# Battery_Management_System.net
KiCad netlist of a schematic drawn in Altium Designer
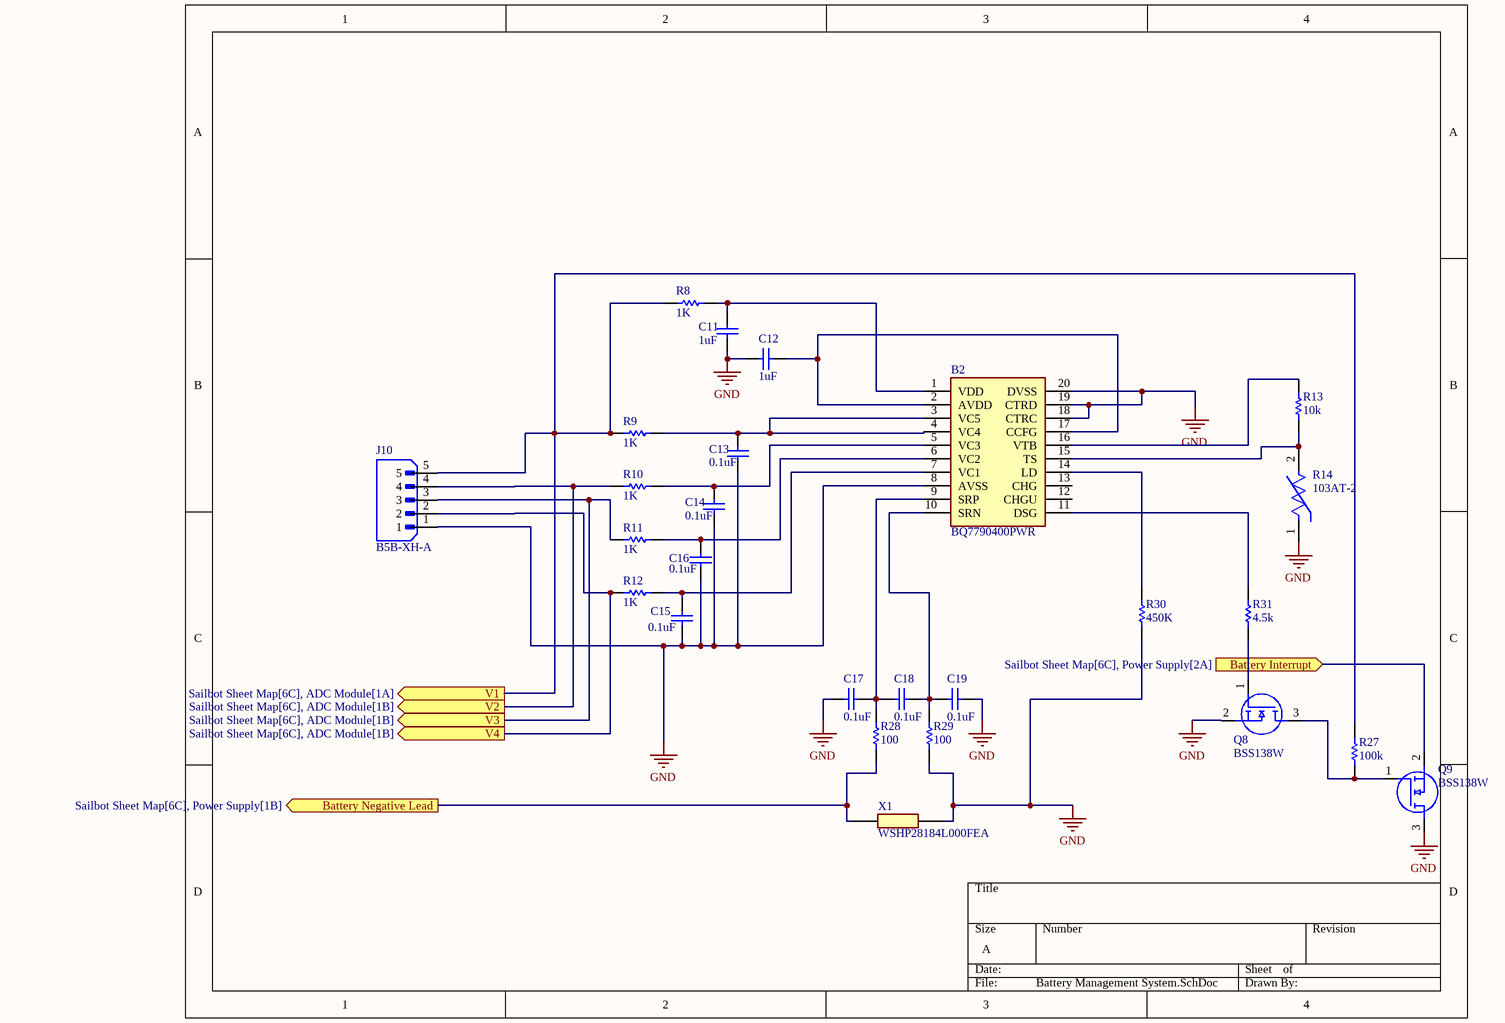
[diagram p0: Battery Management System.SchDoc]

(export (version "E")
  (design (tool "Eeschema 10.0.6"))
  (components
    (comp (ref "B2")
      (value "BQ7790400PWR")
      (footprint "SOP65P640X120-20N")
      (description "3-4S Low Power Protector")
      (fields (field (name "MOUSER PART NUMBER") "595-BQ7790400PWR"))
      (libsource (lib "Sailbot Library") (part "BQ7790400PWR"))
    )
    (comp (ref "C11")
      (value "1uF")
      (footprint "C0805")
      (description "Capacitor")
      (libsource (lib "Simulation Generic Components") (part "Capacitor"))
    )
    (comp (ref "C12")
      (value "1uF")
      (footprint "C0805")
      (description "Capacitor")
      (libsource (lib "Simulation Generic Components") (part "Capacitor"))
    )
    (comp (ref "C13")
      (value "0.1uF")
      (footprint "C0805")
      (description "Capacitor")
      (libsource (lib "Simulation Generic Components") (part "Capacitor"))
    )
    (comp (ref "C14")
      (value "0.1uF")
      (footprint "C0805")
      (description "Capacitor")
      (libsource (lib "Simulation Generic Components") (part "Capacitor"))
    )
    (comp (ref "C15")
      (value "0.1uF")
      (footprint "C0805")
      (description "Capacitor")
      (libsource (lib "Simulation Generic Components") (part "Capacitor"))
    )
    (comp (ref "C16")
      (value "0.1uF")
      (footprint "C0805")
      (description "Capacitor")
      (libsource (lib "Simulation Generic Components") (part "Capacitor"))
    )
    (comp (ref "C17")
      (value "0.1uF")
      (footprint "C0805")
      (description "Capacitor")
      (libsource (lib "Simulation Generic Components") (part "Capacitor"))
    )
    (comp (ref "C18")
      (value "0.1uF")
      (footprint "C0805")
      (description "Capacitor")
      (libsource (lib "Simulation Generic Components") (part "Capacitor"))
    )
    (comp (ref "C19")
      (value "0.1uF")
      (footprint "C0805")
      (description "Capacitor")
      (libsource (lib "Simulation Generic Components") (part "Capacitor"))
    )
    (comp (ref "J10")
      (value "B5B-XH-A")
      (footprint "JST_B5B-XH-A")
      (description "Connector Header Through Hole 5 position 0.098 (2.50mm)")
      (fields (field (name "MF") "JST Sales"))
      (libsource (lib "B5B-XH-A") (part "B5B-XH-A"))
    )
    (comp (ref "Q8")
      (value "BSS138W")
      (footprint "SailbotPCBLib:SOT65P210X110-3N")
      (description "BSS138W N-Channel MOSFET, 210 mA, 50 V, 3-Pin SOT-323 ON Semiconductor")
      (fields (field (name "MOUSER PART NUMBER") "512-BSS138W"))
      (libsource (lib "BSS138W") (part "BSS138W"))
    )
    (comp (ref "Q9")
      (value "BSS138W")
      (footprint "SailbotPCBLib:SOT65P210X110-3N")
      (description "BSS138W N-Channel MOSFET, 210 mA, 50 V, 3-Pin SOT-323 ON Semiconductor")
      (fields (field (name "MOUSER PART NUMBER") "512-BSS138W"))
      (libsource (lib "BSS138W") (part "BSS138W"))
    )
    (comp (ref "R8")
      (value "1K")
      (footprint "6-0805_M")
      (description "Resistor")
      (libsource (lib "Simulation Generic Components") (part "Resistor"))
    )
    (comp (ref "R9")
      (value "1K")
      (footprint "6-0805_M")
      (description "Resistor")
      (libsource (lib "Simulation Generic Components") (part "Resistor"))
    )
    (comp (ref "R10")
      (value "1K")
      (footprint "6-0805_M")
      (description "Resistor")
      (libsource (lib "Simulation Generic Components") (part "Resistor"))
    )
    (comp (ref "R11")
      (value "1K")
      (footprint "6-0805_M")
      (description "Resistor")
      (libsource (lib "Simulation Generic Components") (part "Resistor"))
    )
    (comp (ref "R12")
      (value "1K")
      (footprint "6-0805_M")
      (description "Resistor")
      (libsource (lib "Simulation Generic Components") (part "Resistor"))
    )
    (comp (ref "R13")
      (value "10k")
      (footprint "6-0805_M")
      (description "Resistor")
      (libsource (lib "Simulation Generic Components") (part "Resistor"))
    )
    (comp (ref "R14")
      (value "103AT-2")
      (footprint "FP-103AT-2-MFG")
      (description "Thermistor NTC 10KOhm 1% 2-Pin")
      (fields (field (name "TOLERANCE") "1%"))
      (libsource (lib "Altium Content Vault") (part "3b148a6ebabc5fb4d708a66c052d352"))
    )
    (comp (ref "R27")
      (value "100k")
      (footprint "6-0805_M")
      (description "Resistor")
      (libsource (lib "Simulation Generic Components") (part "Resistor"))
    )
    (comp (ref "R28")
      (value "100")
      (footprint "6-0805_M")
      (description "Resistor")
      (libsource (lib "Simulation Generic Components") (part "Resistor"))
    )
    (comp (ref "R29")
      (value "100")
      (footprint "6-0805_M")
      (description "Resistor")
      (libsource (lib "Simulation Generic Components") (part "Resistor"))
    )
    (comp (ref "R30")
      (value "450K")
      (footprint "6-0805_M")
      (description "Resistor")
      (libsource (lib "Simulation Generic Components") (part "Resistor"))
    )
    (comp (ref "R31")
      (value "4.5k")
      (footprint "6-0805_M")
      (description "Resistor")
      (libsource (lib "Simulation Generic Components") (part "Resistor"))
    )
    (comp (ref "X1")
      (value "WSHP28184L000FEA")
      (footprint "WSHP28184L000FEA")
      (description "Current Sense Resistors - SMD 10W .004ohms 1%")
      (fields (field (name "MOUSER PART NUMBER") "71-WSHP28184L000FEA"))
      (libsource (lib "Sailbot Library") (part "WSHP28184L000FEA"))
    )
  )
  (nets
    (net (code "1") (name "/Battery Interrupt") (class "Default")
      (node (ref "Q9") (pin "2") (pinfunction "S_2") (pintype "passive"))
    )
    (net (code "2") (name "/Battery Negative Lead") (class "Default")
      (node (ref "R28") (pin "1") (pinfunction "1_1") (pintype "passive"))
      (node (ref "X1") (pin "1") (pinfunction "1_1") (pintype "passive"))
    )
    (net (code "3") (name "/V1") (class "Default")
      (node (ref "J10") (pin "5") (pinfunction "5_5") (pintype "passive"))
      (node (ref "R27") (pin "2") (pinfunction "2_2") (pintype "passive"))
      (node (ref "R8") (pin "1") (pinfunction "1_1") (pintype "passive"))
      (node (ref "R9") (pin "1") (pinfunction "1_1") (pintype "passive"))
    )
    (net (code "4") (name "/V2") (class "Default")
      (node (ref "J10") (pin "4") (pinfunction "4_4") (pintype "passive"))
      (node (ref "R10") (pin "1") (pinfunction "1_1") (pintype "passive"))
    )
    (net (code "5") (name "/V3") (class "Default")
      (node (ref "J10") (pin "3") (pinfunction "3_3") (pintype "passive"))
      (node (ref "R11") (pin "1") (pinfunction "1_1") (pintype "passive"))
    )
    (net (code "6") (name "/V4") (class "Default")
      (node (ref "J10") (pin "2") (pinfunction "2_2") (pintype "passive"))
      (node (ref "R12") (pin "1") (pinfunction "1_1") (pintype "passive"))
    )
    (net (code "7") (name "GND") (class "Default")
      (node (ref "B2") (pin "18") (pinfunction "CTRC_18") (pintype "passive"))
      (node (ref "B2") (pin "19") (pinfunction "CTRD_19") (pintype "passive"))
      (node (ref "B2") (pin "20") (pinfunction "DVSS_20") (pintype "passive"))
      (node (ref "B2") (pin "8") (pinfunction "AVSS_8") (pintype "passive"))
      (node (ref "C11") (pin "1") (pinfunction "1_1") (pintype "passive"))
      (node (ref "C12") (pin "2") (pinfunction "2_2") (pintype "passive"))
      (node (ref "C13") (pin "1") (pinfunction "1_1") (pintype "passive"))
      (node (ref "C14") (pin "1") (pinfunction "1_1") (pintype "passive"))
      (node (ref "C15") (pin "1") (pinfunction "1_1") (pintype "passive"))
      (node (ref "C16") (pin "1") (pinfunction "1_1") (pintype "passive"))
      (node (ref "C17") (pin "2") (pinfunction "2_2") (pintype "passive"))
      (node (ref "C19") (pin "1") (pinfunction "1_1") (pintype "passive"))
      (node (ref "J10") (pin "1") (pinfunction "1_1") (pintype "passive"))
      (node (ref "Q8") (pin "2") (pinfunction "S_2") (pintype "passive"))
      (node (ref "Q9") (pin "3") (pinfunction "D_3") (pintype "passive"))
      (node (ref "R14") (pin "1") (pinfunction "1_1") (pintype "passive"))
      (node (ref "R29") (pin "1") (pinfunction "1_1") (pintype "passive"))
      (node (ref "R30") (pin "1") (pinfunction "1_1") (pintype "passive"))
      (node (ref "X1") (pin "2") (pinfunction "2_2") (pintype "passive"))
    )
    (net (code "8") (name "Net-(B2-AVDD)") (class "Default")
      (node (ref "B2") (pin "17") (pinfunction "CCFG_17") (pintype "passive"))
      (node (ref "B2") (pin "2") (pinfunction "AVDD_2") (pintype "passive"))
      (node (ref "C12") (pin "1") (pinfunction "1_1") (pintype "passive"))
    )
    (net (code "9") (name "Net-(B2-DSG)") (class "Default")
      (node (ref "B2") (pin "11") (pinfunction "DSG_11") (pintype "passive"))
      (node (ref "R31") (pin "2") (pinfunction "2_2") (pintype "passive"))
    )
    (net (code "10") (name "Net-(B2-LD)") (class "Default")
      (node (ref "B2") (pin "14") (pinfunction "LD_14") (pintype "passive"))
      (node (ref "R30") (pin "2") (pinfunction "2_2") (pintype "passive"))
    )
    (net (code "11") (name "Net-(B2-SRN)") (class "Default")
      (node (ref "B2") (pin "10") (pinfunction "SRN_10") (pintype "passive"))
      (node (ref "C18") (pin "1") (pinfunction "1_1") (pintype "passive"))
      (node (ref "C19") (pin "2") (pinfunction "2_2") (pintype "passive"))
      (node (ref "R29") (pin "2") (pinfunction "2_2") (pintype "passive"))
    )
    (net (code "12") (name "Net-(B2-SRP)") (class "Default")
      (node (ref "B2") (pin "9") (pinfunction "SRP_9") (pintype "passive"))
      (node (ref "C17") (pin "1") (pinfunction "1_1") (pintype "passive"))
      (node (ref "C18") (pin "2") (pinfunction "2_2") (pintype "passive"))
      (node (ref "R28") (pin "2") (pinfunction "2_2") (pintype "passive"))
    )
    (net (code "13") (name "Net-(B2-TS)") (class "Default")
      (node (ref "B2") (pin "15") (pinfunction "TS_15") (pintype "passive"))
      (node (ref "R13") (pin "1") (pinfunction "1_1") (pintype "passive"))
      (node (ref "R14") (pin "2") (pinfunction "2_2") (pintype "passive"))
    )
    (net (code "14") (name "Net-(B2-VC1)") (class "Default")
      (node (ref "B2") (pin "7") (pinfunction "VC1_7") (pintype "passive"))
      (node (ref "C15") (pin "2") (pinfunction "2_2") (pintype "passive"))
      (node (ref "R12") (pin "2") (pinfunction "2_2") (pintype "passive"))
    )
    (net (code "15") (name "Net-(B2-VC2)") (class "Default")
      (node (ref "B2") (pin "6") (pinfunction "VC2_6") (pintype "passive"))
      (node (ref "C16") (pin "2") (pinfunction "2_2") (pintype "passive"))
      (node (ref "R11") (pin "2") (pinfunction "2_2") (pintype "passive"))
    )
    (net (code "16") (name "Net-(B2-VC3)") (class "Default")
      (node (ref "B2") (pin "5") (pinfunction "VC3_5") (pintype "passive"))
      (node (ref "C14") (pin "2") (pinfunction "2_2") (pintype "passive"))
      (node (ref "R10") (pin "2") (pinfunction "2_2") (pintype "passive"))
    )
    (net (code "17") (name "Net-(B2-VC4)") (class "Default")
      (node (ref "B2") (pin "3") (pinfunction "VC5_3") (pintype "passive"))
      (node (ref "B2") (pin "4") (pinfunction "VC4_4") (pintype "passive"))
      (node (ref "C13") (pin "2") (pinfunction "2_2") (pintype "passive"))
      (node (ref "R9") (pin "2") (pinfunction "2_2") (pintype "passive"))
    )
    (net (code "18") (name "Net-(B2-VDD)") (class "Default")
      (node (ref "B2") (pin "1") (pinfunction "VDD_1") (pintype "passive"))
      (node (ref "C11") (pin "2") (pinfunction "2_2") (pintype "passive"))
      (node (ref "R8") (pin "2") (pinfunction "2_2") (pintype "passive"))
    )
    (net (code "19") (name "Net-(B2-VTB)") (class "Default")
      (node (ref "B2") (pin "16") (pinfunction "VTB_16") (pintype "passive"))
      (node (ref "R13") (pin "2") (pinfunction "2_2") (pintype "passive"))
    )
    (net (code "20") (name "Net-(Q8-D)") (class "Default")
      (node (ref "Q8") (pin "3") (pinfunction "D_3") (pintype "passive"))
      (node (ref "Q9") (pin "1") (pinfunction "G_1") (pintype "passive"))
      (node (ref "R27") (pin "1") (pinfunction "1_1") (pintype "passive"))
    )
    (net (code "21") (name "Net-(Q8-G)") (class "Default")
      (node (ref "Q8") (pin "1") (pinfunction "G_1") (pintype "passive"))
      (node (ref "R31") (pin "1") (pinfunction "1_1") (pintype "passive"))
    )
    (net (code "22") (name "unconnected-(B2-CHG-Pad13)") (class "Default")
      (node (ref "B2") (pin "13") (pinfunction "CHG_13") (pintype "passive"))
    )
    (net (code "23") (name "unconnected-(B2-CHGU-Pad12)") (class "Default")
      (node (ref "B2") (pin "12") (pinfunction "CHGU_12") (pintype "passive"))
    )
  )
)
